# socket_power_supply.net
KiCad netlist of a schematic drawn in Altium Designer
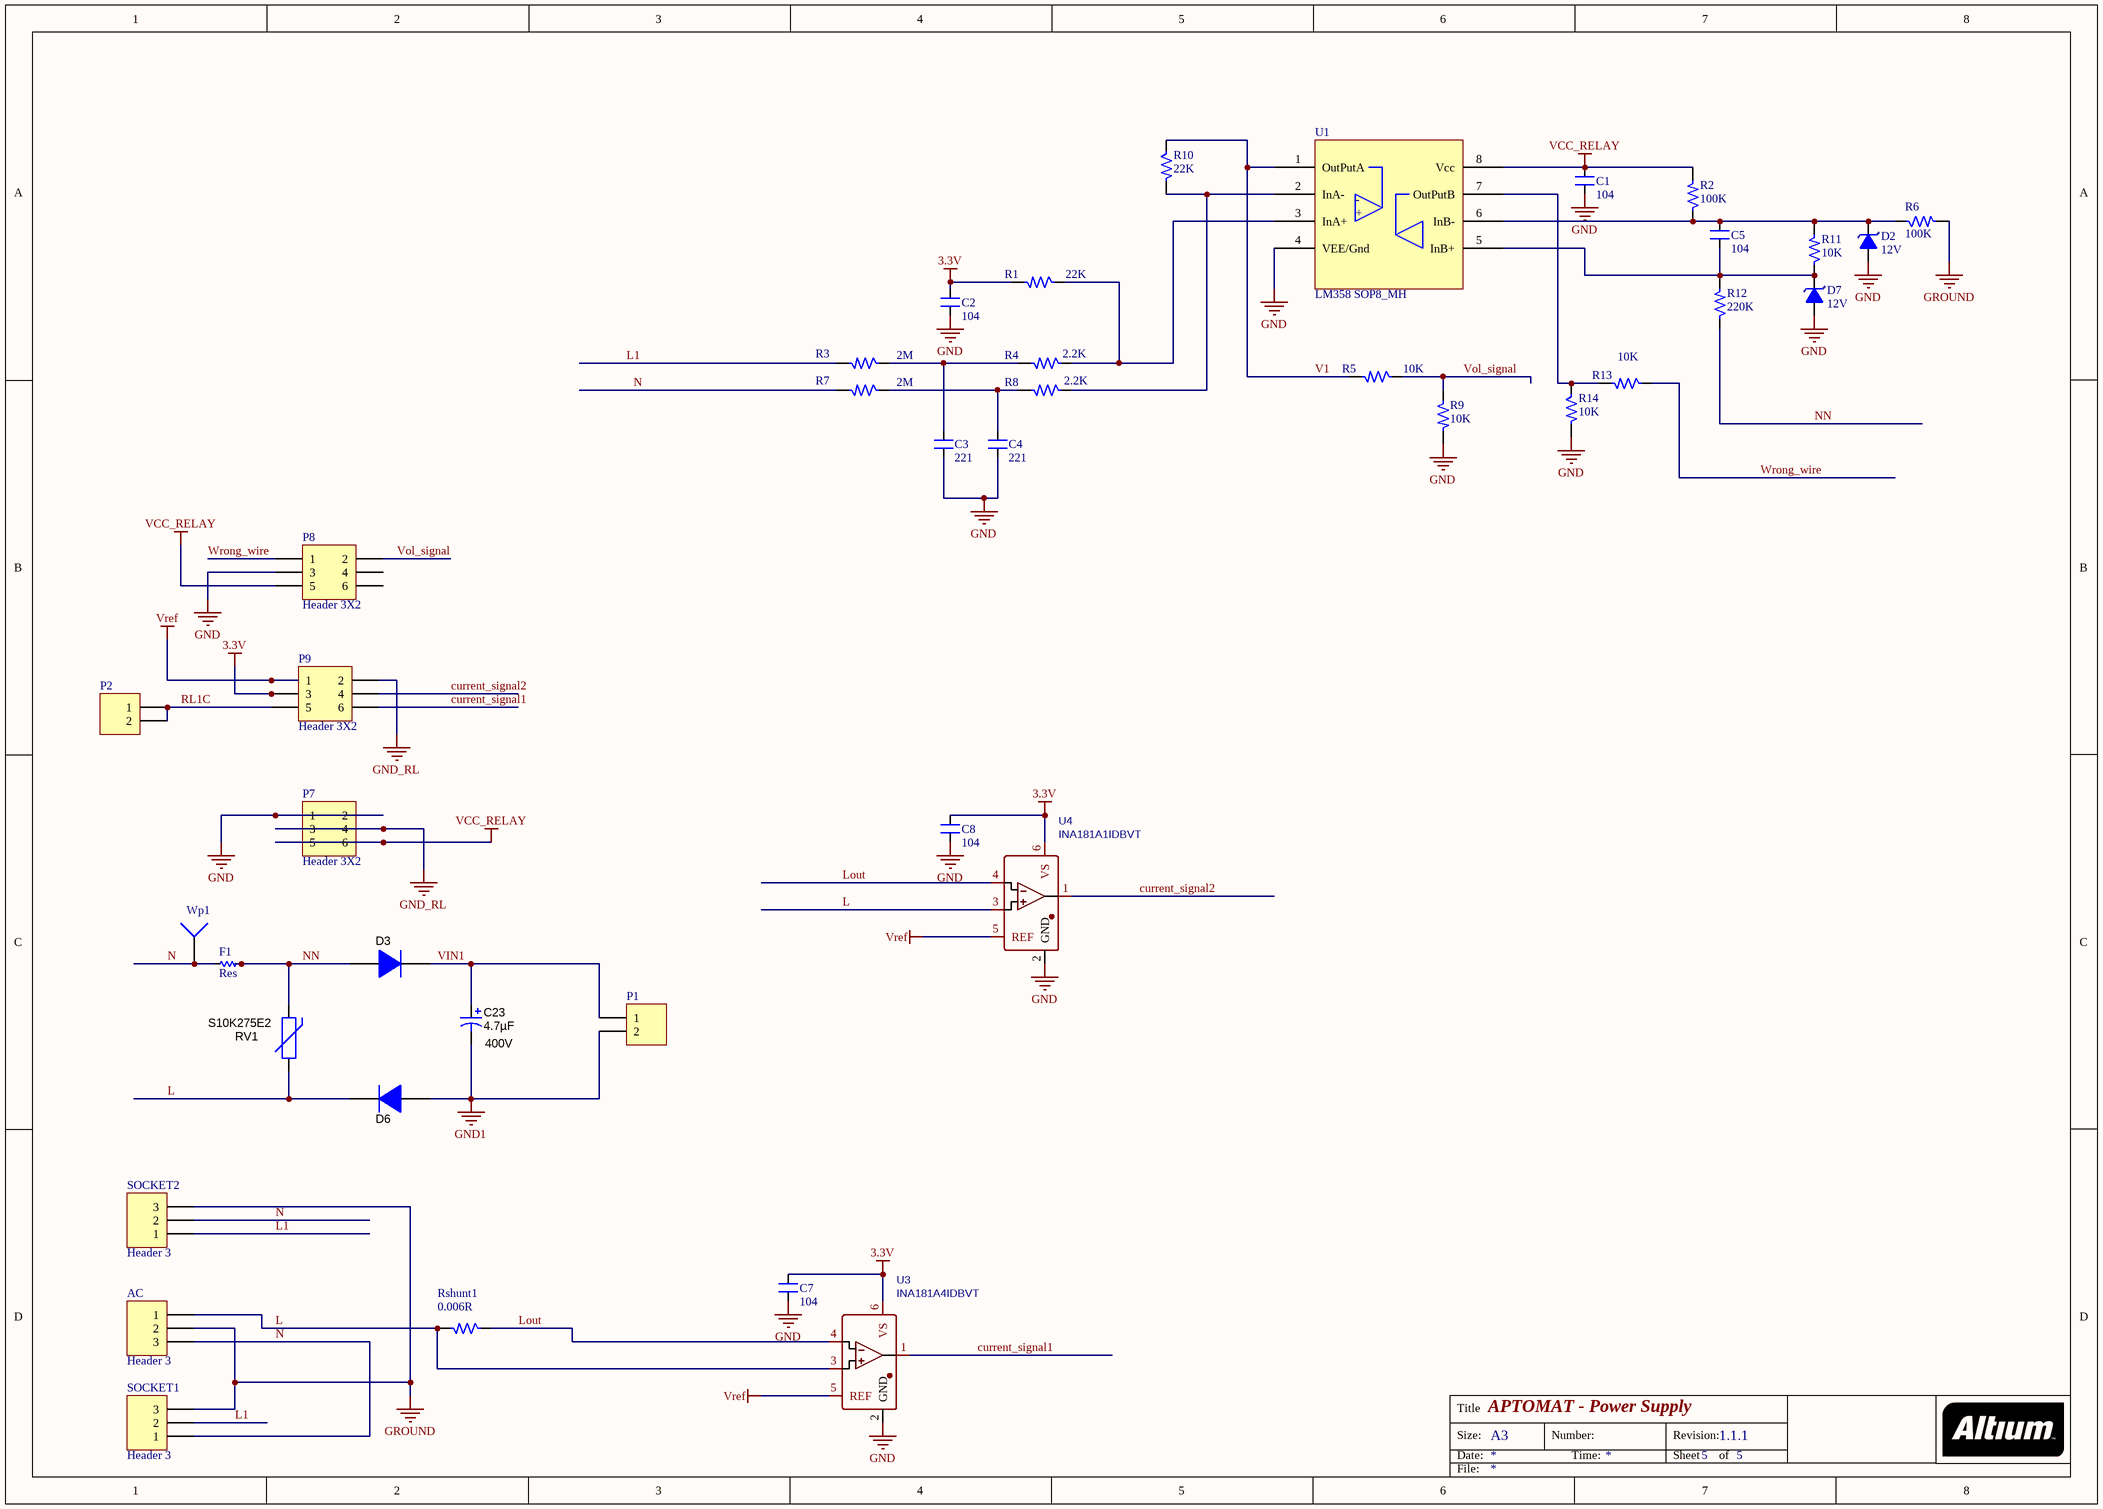
[diagram p0: socket_power_supply.SchDoc]

(export (version "E")
  (design (tool "Eeschema 10.0.6"))
  (components
    (comp (ref "AC")
      (value "Header 3")
      (footprint "CHAN3DONGTO")
      (description "Header, 3-Pin")
      (fields (field (name "PUBLISHER") "Altium Limited"))
      (libsource (lib "") (part "Header 3_1"))
    )
    (comp (ref "C1")
      (value "104")
      (footprint "0805_HV")
      (description "Cap SMD")
      (libsource (lib "hatcatbietbay") (part "CM"))
    )
    (comp (ref "C2")
      (value "104")
      (footprint "0805_HV")
      (description "Cap SMD")
      (libsource (lib "hatcatbietbay") (part "CM"))
    )
    (comp (ref "C3")
      (value "221")
      (footprint "0805_HV")
      (description "Cap SMD")
      (libsource (lib "hatcatbietbay") (part "CM"))
    )
    (comp (ref "C4")
      (value "221")
      (footprint "0805_HV")
      (description "Cap SMD")
      (libsource (lib "hatcatbietbay") (part "CM"))
    )
    (comp (ref "C5")
      (value "104")
      (footprint "0805_HV")
      (description "Cap SMD")
      (libsource (lib "hatcatbietbay") (part "CM"))
    )
    (comp (ref "C7")
      (value "104")
      (footprint "0805_HV")
      (description "Cap SMD")
      (libsource (lib "hatcatbietbay") (part "CM"))
    )
    (comp (ref "C8")
      (value "104")
      (footprint "0805_HV")
      (description "Cap SMD")
      (libsource (lib "hatcatbietbay") (part "CM"))
    )
    (comp (ref "C23")
      (value "400AX6R8M8x11")
      (footprint "PcbLib1:PANACAP-G-GENERIC")
      (description "CAP, AL, 6.8uF, 400V, +/-20%, TH")
      (fields
        (field (name "VALUEDISPLAYED") "4.7µF")
        (field (name "MANUFACTURER") "Rubycon")
        (field (name "VALUE2") "400V")
        (field (name "PUBLISHER") "Texas Instruments")
      )
      (libsource (lib "Capacitor_Aluminum") (part "400AX6R8M8x11"))
    )
    (comp (ref "D2")
      (value "12V")
      (footprint "Diode Zener 1N5359B 5W 24V")
      (description "Diode Zenner 1W 13V 1N4743 DIP")
      (libsource (lib "MH_DA_THU_VIEN_16122016") (part "Diode Zenner 1W 13V 1N4743 DIP_MH"))
    )
    (comp (ref "D3")
      (value "US1M-13-F")
      (footprint "PcbLib1:SMB")
      (description "Diode, Ultrafast, 600V, 1A, SMB")
      (fields (field (name "MANUFACTURER") "Diodes Inc.") (field (name "PUBLISHER") "Texas Instruments"))
      (libsource (lib "Diode") (part "MURS160-13-F"))
    )
    (comp (ref "D6")
      (value "US1M-13-F")
      (footprint "PcbLib1:SMB")
      (description "Diode, Ultrafast, 600V, 1A, SMB")
      (fields (field (name "MANUFACTURER") "Diodes Inc.") (field (name "PUBLISHER") "Texas Instruments"))
      (libsource (lib "Diode") (part "MURS160-13-F"))
    )
    (comp (ref "D7")
      (value "12V")
      (footprint "Diode Zener 1N5359B 5W 24V")
      (description "Diode Zenner 1W 13V 1N4743 DIP")
      (libsource (lib "MH_DA_THU_VIEN_16122016") (part "Diode Zenner 1W 13V 1N4743 DIP_MH"))
    )
    (comp (ref "F1")
      (value "Res")
      (footprint "1206")
      (description "Resistor")
      (fields
        (field (name "MANUFACTURER") "Generic Components")
        (field (name "PUBLISHER") "Altium Hobart Technology Centre")
      )
      (libsource (lib "LIBRARY") (part "Res-SMD"))
    )
    (comp (ref "P1")
      (value "Header 2")
      (footprint "HDR1X2")
      (description "Header, 2-Pin")
      (fields (field (name "PUBLISHER") "Altium Limited"))
      (libsource (lib "Miscellaneous Connectors") (part "Header 2"))
    )
    (comp (ref "P2")
      (value "Header 2")
      (footprint "HDR1X2")
      (description "Header, 2-Pin")
      (fields (field (name "PUBLISHER") "Altium Limited"))
      (libsource (lib "") (part "Header 2_1"))
    )
    (comp (ref "P7")
      (value "Header 3X2")
      (footprint "HDR2X3")
      (description "Header, 3-Pin, Dual row")
      (fields (field (name "PUBLISHER") "Altium Limited"))
      (libsource (lib "Miscellaneous Connectors") (part "Header 3X2"))
    )
    (comp (ref "P8")
      (value "Header 3X2")
      (footprint "HDR2X3")
      (description "Header, 3-Pin, Dual row")
      (fields (field (name "PUBLISHER") "Altium Limited"))
      (libsource (lib "Miscellaneous Connectors") (part "Header 3X2"))
    )
    (comp (ref "P9")
      (value "Header 3X2")
      (footprint "HDR2X3")
      (description "Header, 3-Pin, Dual row")
      (fields (field (name "PUBLISHER") "Altium Limited"))
      (libsource (lib "Miscellaneous Connectors") (part "Header 3X2"))
    )
    (comp (ref "R1")
      (value "22K")
      (footprint "0805_HV")
      (description "Resistor 1/4W")
      (libsource (lib "hatcatbietbay") (part "R"))
    )
    (comp (ref "R2")
      (value "100K")
      (footprint "0805_HV")
      (description "Resistor 1/4W")
      (libsource (lib "hatcatbietbay") (part "R"))
    )
    (comp (ref "R3")
      (value "2M")
      (footprint "1206")
      (description "Resistor 1/4W")
      (libsource (lib "hatcatbietbay") (part "R"))
    )
    (comp (ref "R4")
      (value "2.2K")
      (footprint "0805_HV")
      (description "Resistor 1/4W")
      (libsource (lib "hatcatbietbay") (part "R"))
    )
    (comp (ref "R5")
      (value "10K")
      (footprint "0805_HV")
      (description "Resistor 1/4W")
      (libsource (lib "hatcatbietbay") (part "R"))
    )
    (comp (ref "R6")
      (value "100K")
      (footprint "0805_HV")
      (description "Resistor 1/4W")
      (libsource (lib "hatcatbietbay") (part "R"))
    )
    (comp (ref "R7")
      (value "2M")
      (footprint "1206")
      (description "Resistor 1/4W")
      (libsource (lib "hatcatbietbay") (part "R"))
    )
    (comp (ref "R8")
      (value "2.2K")
      (footprint "0805_HV")
      (description "Resistor 1/4W")
      (libsource (lib "hatcatbietbay") (part "R"))
    )
    (comp (ref "R9")
      (value "10K")
      (footprint "0805_HV")
      (description "Resistor 1/4W")
      (libsource (lib "hatcatbietbay") (part "R"))
    )
    (comp (ref "R10")
      (value "22K")
      (footprint "0805_HV")
      (description "Resistor 1/4W")
      (libsource (lib "hatcatbietbay") (part "R"))
    )
    (comp (ref "R11")
      (value "10K")
      (footprint "0805_HV")
      (description "Resistor 1/4W")
      (libsource (lib "hatcatbietbay") (part "R"))
    )
    (comp (ref "R12")
      (value "220K")
      (footprint "0805_HV")
      (description "Resistor 1/4W")
      (libsource (lib "hatcatbietbay") (part "R"))
    )
    (comp (ref "R13")
      (value "10K")
      (footprint "0805_HV")
      (description "Resistor 1/4W")
      (libsource (lib "hatcatbietbay") (part "R"))
    )
    (comp (ref "R14")
      (value "10K")
      (footprint "0805_HV")
      (description "Resistor 1/4W")
      (libsource (lib "hatcatbietbay") (part "R"))
    )
    (comp (ref "Rshunt1")
      (value "0.006R")
      (footprint "RESC2728")
      (description "Resistor 1/4W")
      (libsource (lib "hatcatbietbay") (part "R"))
    )
    (comp (ref "RV1")
      (value "S10K275E2")
      (footprint "PcbLib1:VAR_S10K275E2")
      (description "Varistor 275V RMS 10MM Radial, TH")
      (fields
        (field (name "MANUFACTURER") "EPCOS Inc")
        (field (name "SYMBOLCREATOR") "a0412235")
        (field (name "PUBLISHER") "Texas Instruments")
      )
      (libsource (lib "Other_Passive") (part "S10K275E2"))
    )
    (comp (ref "SOCKET1")
      (value "Header 3")
      (footprint "socket")
      (description "Header, 3-Pin")
      (fields (field (name "PUBLISHER") "Altium Limited"))
      (libsource (lib "Miscellaneous Connectors") (part "Header 3"))
    )
    (comp (ref "SOCKET2")
      (value "Header 3")
      (footprint "socket")
      (description "Header, 3-Pin")
      (fields (field (name "PUBLISHER") "Altium Limited"))
      (libsource (lib "Miscellaneous Connectors") (part "Header 3"))
    )
    (comp (ref "U1")
      (value "LM358 SOP8_MH")
      (footprint "SOP 8")
      (libsource (lib "MH_DA_THU_VIEN_16122016") (part "LM358 SOP8_MH"))
    )
    (comp (ref "U3")
      (value "INA181A4IDBVT")
      (footprint "SOT95P280X145-6N")
      (fields
        (field (name "BOM_SUPPLIER PART") "C116200")
        (field (name "BOM_MANUFACTURER PART") "INA181A2IDBVT")
        (field (name "CONTRIBUTOR") "LCSC")
      )
      (libsource (lib "Schlib1") (part "INA181"))
    )
    (comp (ref "U4")
      (value "INA181A1IDBVT")
      (footprint "SOT95P280X145-6N")
      (fields
        (field (name "BOM_SUPPLIER PART") "C116200")
        (field (name "BOM_MANUFACTURER PART") "INA181A2IDBVT")
        (field (name "CONTRIBUTOR") "LCSC")
      )
      (libsource (lib "Schlib1") (part "INA181"))
    )
    (comp (ref "Wp1")
      (value "Socket")
      (footprint "PIN1")
      (fields (field (name "PUBLISHER") "Altium Limited"))
      (libsource (lib "Miscellaneous Connectors") (part "Socket"))
    )
  )
  (nets
    (net (code "1") (name "/L") (class "Default")
      (node (ref "AC") (pin "1") (pinfunction "1_1") (pintype "passive"))
      (node (ref "D6") (pin "1") (pinfunction "K_1") (pintype "passive"))
      (node (ref "RV1") (pin "1") (pinfunction "1_1") (pintype "passive"))
      (node (ref "Rshunt1") (pin "2") (pinfunction "2_2") (pintype "passive"))
      (node (ref "U3") (pin "3") (pinfunction "IN+_3") (pintype "passive"))
      (node (ref "U4") (pin "3") (pinfunction "IN+_3") (pintype "passive"))
    )
    (net (code "2") (name "/L1") (class "Default")
      (node (ref "R3") (pin "2") (pinfunction "2_2") (pintype "passive"))
      (node (ref "SOCKET1") (pin "2") (pinfunction "2_2") (pintype "passive"))
      (node (ref "SOCKET2") (pin "1") (pinfunction "1_1") (pintype "passive"))
    )
    (net (code "3") (name "/Lout") (class "Default")
      (node (ref "Rshunt1") (pin "1") (pinfunction "1_1") (pintype "passive"))
      (node (ref "U3") (pin "4") (pinfunction "IN-_4") (pintype "passive"))
      (node (ref "U4") (pin "4") (pinfunction "IN-_4") (pintype "passive"))
    )
    (net (code "4") (name "/N") (class "Default")
      (node (ref "AC") (pin "3") (pinfunction "3_3") (pintype "passive"))
      (node (ref "F1") (pin "2") (pinfunction "2_2") (pintype "passive"))
      (node (ref "R7") (pin "2") (pinfunction "2_2") (pintype "passive"))
      (node (ref "SOCKET1") (pin "1") (pinfunction "1_1") (pintype "passive"))
      (node (ref "SOCKET2") (pin "2") (pinfunction "2_2") (pintype "passive"))
      (node (ref "Wp1") (pin "1") (pinfunction "1_1") (pintype "passive"))
    )
    (net (code "5") (name "/NN") (class "Default")
      (node (ref "D3") (pin "2") (pinfunction "A_2") (pintype "passive"))
      (node (ref "F1") (pin "1") (pinfunction "1_1") (pintype "passive"))
      (node (ref "R12") (pin "1") (pinfunction "1_1") (pintype "passive"))
      (node (ref "RV1") (pin "2") (pinfunction "2_2") (pintype "passive"))
    )
    (net (code "6") (name "/RL1C") (class "Default")
      (node (ref "P2") (pin "1") (pinfunction "1_1") (pintype "passive"))
      (node (ref "P2") (pin "2") (pinfunction "2_2") (pintype "passive"))
      (node (ref "P9") (pin "5") (pinfunction "5_5") (pintype "passive"))
    )
    (net (code "7") (name "/V1") (class "Default")
      (node (ref "R10") (pin "1") (pinfunction "1_1") (pintype "passive"))
      (node (ref "R5") (pin "2") (pinfunction "2_2") (pintype "passive"))
      (node (ref "U1") (pin "1") (pinfunction "OutPutA_1") (pintype "passive"))
    )
    (net (code "8") (name "/VIN1") (class "Default")
      (node (ref "C23") (pin "1") (pinfunction "+_1") (pintype "passive"))
      (node (ref "D3") (pin "1") (pinfunction "K_1") (pintype "passive"))
      (node (ref "P1") (pin "1") (pinfunction "1_1") (pintype "passive"))
    )
    (net (code "9") (name "/Vol_signal") (class "Default")
      (node (ref "P8") (pin "2") (pinfunction "2_2") (pintype "passive"))
      (node (ref "R5") (pin "1") (pinfunction "1_1") (pintype "passive"))
      (node (ref "R9") (pin "1") (pinfunction "1_1") (pintype "passive"))
    )
    (net (code "10") (name "/Wrong_wire") (class "Default")
      (node (ref "P8") (pin "1") (pinfunction "1_1") (pintype "passive"))
      (node (ref "R13") (pin "1") (pinfunction "1_1") (pintype "passive"))
    )
    (net (code "11") (name "/current_signal1") (class "Default")
      (node (ref "P9") (pin "6") (pinfunction "6_6") (pintype "passive"))
      (node (ref "U3") (pin "1") (pinfunction "OUT_1") (pintype "passive"))
    )
    (net (code "12") (name "/current_signal2") (class "Default")
      (node (ref "P9") (pin "4") (pinfunction "4_4") (pintype "passive"))
      (node (ref "U4") (pin "1") (pinfunction "OUT_1") (pintype "passive"))
    )
    (net (code "13") (name "3.3V") (class "Default")
      (node (ref "C2") (pin "2") (pinfunction "2_2") (pintype "passive"))
      (node (ref "C7") (pin "2") (pinfunction "2_2") (pintype "passive"))
      (node (ref "C8") (pin "2") (pinfunction "2_2") (pintype "passive"))
      (node (ref "P9") (pin "3") (pinfunction "3_3") (pintype "passive"))
      (node (ref "R1") (pin "2") (pinfunction "2_2") (pintype "passive"))
      (node (ref "U3") (pin "6") (pinfunction "VS_6") (pintype "passive"))
      (node (ref "U4") (pin "6") (pinfunction "VS_6") (pintype "passive"))
    )
    (net (code "14") (name "GND") (class "Default")
      (node (ref "C1") (pin "1") (pinfunction "1_1") (pintype "passive"))
      (node (ref "C2") (pin "1") (pinfunction "1_1") (pintype "passive"))
      (node (ref "C3") (pin "1") (pinfunction "1_1") (pintype "passive"))
      (node (ref "C4") (pin "1") (pinfunction "1_1") (pintype "passive"))
      (node (ref "C7") (pin "1") (pinfunction "1_1") (pintype "passive"))
      (node (ref "C8") (pin "1") (pinfunction "1_1") (pintype "passive"))
      (node (ref "D2") (pin "1") (pinfunction "A_1") (pintype "passive"))
      (node (ref "D7") (pin "1") (pinfunction "A_1") (pintype "passive"))
      (node (ref "P7") (pin "1") (pinfunction "1_1") (pintype "passive"))
      (node (ref "P7") (pin "2") (pinfunction "2_2") (pintype "passive"))
      (node (ref "P8") (pin "3") (pinfunction "3_3") (pintype "passive"))
      (node (ref "R14") (pin "2") (pinfunction "2_2") (pintype "passive"))
      (node (ref "R9") (pin "2") (pinfunction "2_2") (pintype "passive"))
      (node (ref "U1") (pin "4") (pinfunction "VEE/Gnd_4") (pintype "passive"))
      (node (ref "U3") (pin "2") (pinfunction "GND_2") (pintype "passive"))
      (node (ref "U4") (pin "2") (pinfunction "GND_2") (pintype "passive"))
    )
    (net (code "15") (name "GND1") (class "Default")
      (node (ref "C23") (pin "2") (pinfunction "-_2") (pintype "passive"))
      (node (ref "D6") (pin "2") (pinfunction "A_2") (pintype "passive"))
      (node (ref "P1") (pin "2") (pinfunction "2_2") (pintype "passive"))
    )
    (net (code "16") (name "GND_RL") (class "Default")
      (node (ref "P7") (pin "3") (pinfunction "3_3") (pintype "passive"))
      (node (ref "P7") (pin "4") (pinfunction "4_4") (pintype "passive"))
      (node (ref "P9") (pin "2") (pinfunction "2_2") (pintype "passive"))
    )
    (net (code "17") (name "GROUND") (class "Default")
      (node (ref "AC") (pin "2") (pinfunction "2_2") (pintype "passive"))
      (node (ref "R6") (pin "2") (pinfunction "2_2") (pintype "passive"))
      (node (ref "SOCKET1") (pin "3") (pinfunction "3_3") (pintype "passive"))
      (node (ref "SOCKET2") (pin "3") (pinfunction "3_3") (pintype "passive"))
    )
    (net (code "18") (name "Net-(C3-Pad2)") (class "Default")
      (node (ref "C3") (pin "2") (pinfunction "2_2") (pintype "passive"))
      (node (ref "R3") (pin "1") (pinfunction "1_1") (pintype "passive"))
      (node (ref "R4") (pin "2") (pinfunction "2_2") (pintype "passive"))
    )
    (net (code "19") (name "Net-(C4-Pad2)") (class "Default")
      (node (ref "C4") (pin "2") (pinfunction "2_2") (pintype "passive"))
      (node (ref "R7") (pin "1") (pinfunction "1_1") (pintype "passive"))
      (node (ref "R8") (pin "2") (pinfunction "2_2") (pintype "passive"))
    )
    (net (code "20") (name "Net-(D2-K)") (class "Default")
      (node (ref "C5") (pin "2") (pinfunction "2_2") (pintype "passive"))
      (node (ref "D2") (pin "2") (pinfunction "K_2") (pintype "passive"))
      (node (ref "R11") (pin "2") (pinfunction "2_2") (pintype "passive"))
      (node (ref "R2") (pin "1") (pinfunction "1_1") (pintype "passive"))
      (node (ref "R6") (pin "1") (pinfunction "1_1") (pintype "passive"))
      (node (ref "U1") (pin "6") (pinfunction "InB-_6") (pintype "passive"))
    )
    (net (code "21") (name "Net-(D7-K)") (class "Default")
      (node (ref "C5") (pin "1") (pinfunction "1_1") (pintype "passive"))
      (node (ref "D7") (pin "2") (pinfunction "K_2") (pintype "passive"))
      (node (ref "R11") (pin "1") (pinfunction "1_1") (pintype "passive"))
      (node (ref "R12") (pin "2") (pinfunction "2_2") (pintype "passive"))
      (node (ref "U1") (pin "5") (pinfunction "InB+_5") (pintype "passive"))
    )
    (net (code "22") (name "Net-(U1-InA+)") (class "Default")
      (node (ref "R1") (pin "1") (pinfunction "1_1") (pintype "passive"))
      (node (ref "R4") (pin "1") (pinfunction "1_1") (pintype "passive"))
      (node (ref "U1") (pin "3") (pinfunction "InA+_3") (pintype "passive"))
    )
    (net (code "23") (name "Net-(U1-InA-)") (class "Default")
      (node (ref "R10") (pin "2") (pinfunction "2_2") (pintype "passive"))
      (node (ref "R8") (pin "1") (pinfunction "1_1") (pintype "passive"))
      (node (ref "U1") (pin "2") (pinfunction "InA-_2") (pintype "passive"))
    )
    (net (code "24") (name "Net-(U1-OutPutB)") (class "Default")
      (node (ref "R13") (pin "2") (pinfunction "2_2") (pintype "passive"))
      (node (ref "R14") (pin "1") (pinfunction "1_1") (pintype "passive"))
      (node (ref "U1") (pin "7") (pinfunction "OutPutB_7") (pintype "passive"))
    )
    (net (code "25") (name "VCC_RELAY") (class "Default")
      (node (ref "C1") (pin "2") (pinfunction "2_2") (pintype "passive"))
      (node (ref "P7") (pin "5") (pinfunction "5_5") (pintype "passive"))
      (node (ref "P7") (pin "6") (pinfunction "6_6") (pintype "passive"))
      (node (ref "P8") (pin "5") (pinfunction "5_5") (pintype "passive"))
      (node (ref "R2") (pin "2") (pinfunction "2_2") (pintype "passive"))
      (node (ref "U1") (pin "8") (pinfunction "Vcc_8") (pintype "passive"))
    )
    (net (code "26") (name "Vref") (class "Default")
      (node (ref "P9") (pin "1") (pinfunction "1_1") (pintype "passive"))
      (node (ref "U3") (pin "5") (pinfunction "REF_5") (pintype "passive"))
      (node (ref "U4") (pin "5") (pinfunction "REF_5") (pintype "passive"))
    )
    (net (code "27") (name "unconnected-(P8-Pad4)") (class "Default")
      (node (ref "P8") (pin "4") (pinfunction "4_4") (pintype "passive"))
    )
    (net (code "28") (name "unconnected-(P8-Pad6)") (class "Default")
      (node (ref "P8") (pin "6") (pinfunction "6_6") (pintype "passive"))
    )
  )
)
